# LED_Strip_Board_Schematic.net
KiCad netlist of a schematic drawn in Altium Designer
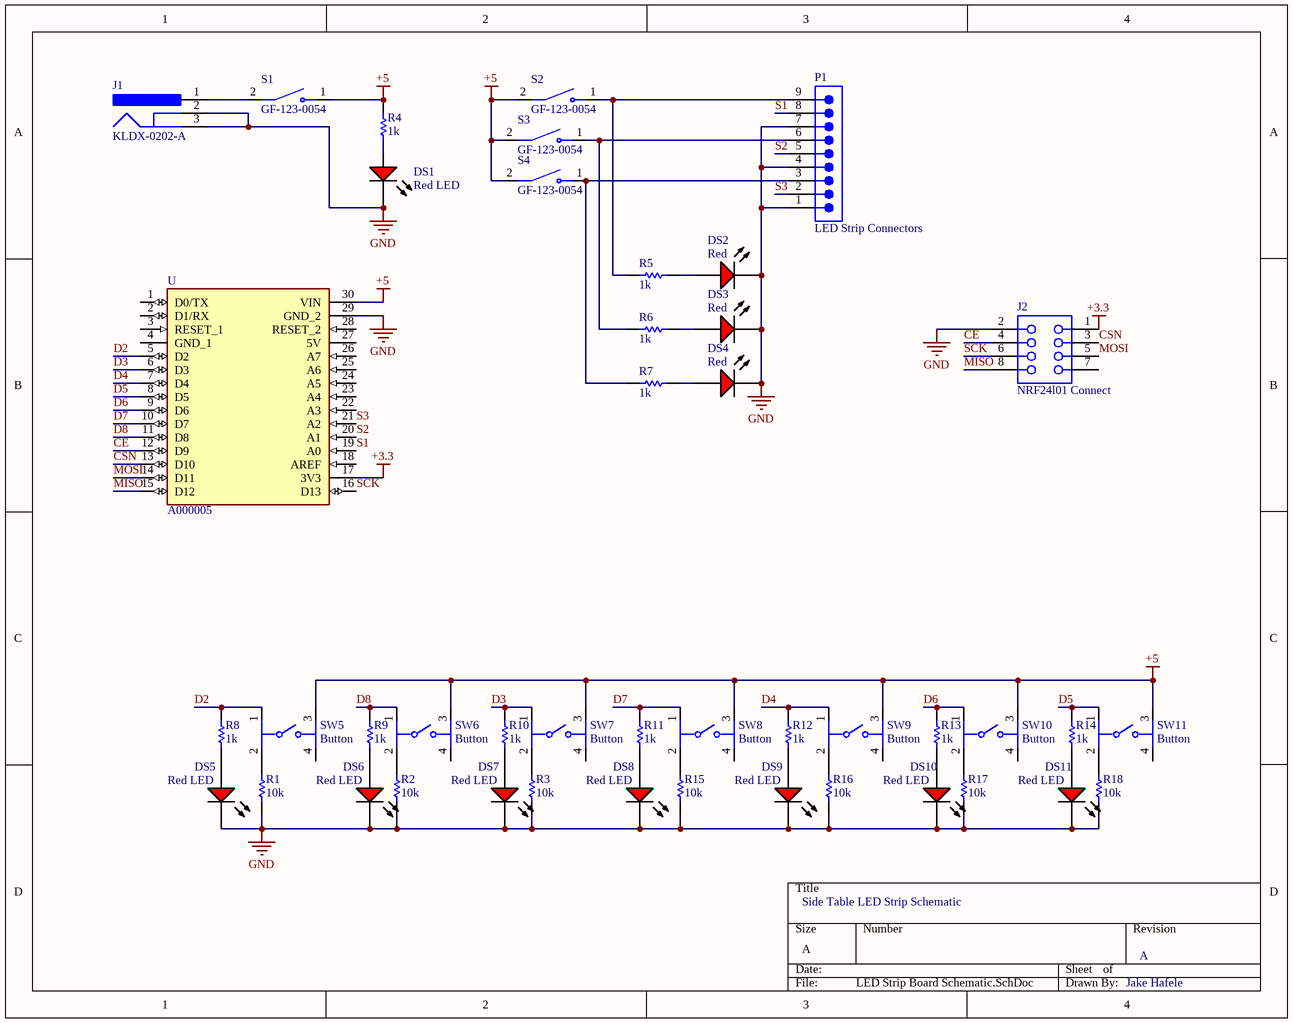
[diagram p0: LED Strip Board Schematic.SchDoc]

(export (version "E")
  (design (tool "Eeschema 10.0.6"))
  (components
    (comp (ref "DS1")
      (value "Red LED")
      (footprint "VISH-TLMS1000_V")
      (description "Low Current LED, 40 mW, 1.8 V, -40 to 100 degC, 2-Pin SMD (0603), RoHS, Tape and Reel")
      (fields (field (name "MANUFACTURER") "Vishay"))
      (libsource (lib "Altium Content Vault") (part "LED-RED-AK-2"))
    )
    (comp (ref "DS2")
      (value "Red")
      (footprint "VISH-TLMS1000_V")
      (description "Low Current LED, 40 mW, 1.8 V, -40 to 100 degC, 2-Pin SMD (0603), RoHS, Tape and Reel")
      (fields (field (name "MANUFACTURER") "Vishay"))
      (libsource (lib "Altium Content Vault") (part "LED-RED-AK-2"))
    )
    (comp (ref "DS3")
      (value "Red")
      (footprint "VISH-TLMS1000_V")
      (description "Low Current LED, 40 mW, 1.8 V, -40 to 100 degC, 2-Pin SMD (0603), RoHS, Tape and Reel")
      (fields (field (name "MANUFACTURER") "Vishay"))
      (libsource (lib "Altium Content Vault") (part "LED-RED-AK-2"))
    )
    (comp (ref "DS4")
      (value "Red")
      (footprint "VISH-TLMS1000_V")
      (description "Low Current LED, 40 mW, 1.8 V, -40 to 100 degC, 2-Pin SMD (0603), RoHS, Tape and Reel")
      (fields (field (name "MANUFACTURER") "Vishay"))
      (libsource (lib "Altium Content Vault") (part "LED-RED-AK-2"))
    )
    (comp (ref "DS5")
      (value "Red LED")
      (footprint "VISH-TLMS1000_V")
      (description "Low Current LED, 40 mW, 1.8 V, -40 to 100 degC, 2-Pin SMD (0603), RoHS, Tape and Reel")
      (fields (field (name "MANUFACTURER") "Vishay"))
      (libsource (lib "Altium Content Vault") (part "LED-RED-AK-2"))
    )
    (comp (ref "DS6")
      (value "Red LED")
      (footprint "VISH-TLMS1000_V")
      (description "Low Current LED, 40 mW, 1.8 V, -40 to 100 degC, 2-Pin SMD (0603), RoHS, Tape and Reel")
      (fields (field (name "MANUFACTURER") "Vishay"))
      (libsource (lib "Altium Content Vault") (part "LED-RED-AK-2"))
    )
    (comp (ref "DS7")
      (value "Red LED")
      (footprint "VISH-TLMS1000_V")
      (description "Low Current LED, 40 mW, 1.8 V, -40 to 100 degC, 2-Pin SMD (0603), RoHS, Tape and Reel")
      (fields (field (name "MANUFACTURER") "Vishay"))
      (libsource (lib "Altium Content Vault") (part "LED-RED-AK-2"))
    )
    (comp (ref "DS8")
      (value "Red LED")
      (footprint "VISH-TLMS1000_V")
      (description "Low Current LED, 40 mW, 1.8 V, -40 to 100 degC, 2-Pin SMD (0603), RoHS, Tape and Reel")
      (fields (field (name "MANUFACTURER") "Vishay"))
      (libsource (lib "Altium Content Vault") (part "LED-RED-AK-2"))
    )
    (comp (ref "DS9")
      (value "Red LED")
      (footprint "VISH-TLMS1000_V")
      (description "Low Current LED, 40 mW, 1.8 V, -40 to 100 degC, 2-Pin SMD (0603), RoHS, Tape and Reel")
      (fields (field (name "MANUFACTURER") "Vishay"))
      (libsource (lib "Altium Content Vault") (part "LED-RED-AK-2"))
    )
    (comp (ref "DS10")
      (value "Red LED")
      (footprint "VISH-TLMS1000_V")
      (description "Low Current LED, 40 mW, 1.8 V, -40 to 100 degC, 2-Pin SMD (0603), RoHS, Tape and Reel")
      (fields (field (name "MANUFACTURER") "Vishay"))
      (libsource (lib "Altium Content Vault") (part "LED-RED-AK-2"))
    )
    (comp (ref "DS11")
      (value "Red LED")
      (footprint "VISH-TLMS1000_V")
      (description "Low Current LED, 40 mW, 1.8 V, -40 to 100 degC, 2-Pin SMD (0603), RoHS, Tape and Reel")
      (fields (field (name "MANUFACTURER") "Vishay"))
      (libsource (lib "Altium Content Vault") (part "LED-RED-AK-2"))
    )
    (comp (ref "J1")
      (value "KLDX-0202-A")
      (footprint "KYCN-KLDX-0202-A_V")
      (description "DC Power Jack, 24 V, 3.5 A, -25 to 85 degC, 3-Pin THD, RoHS")
      (fields (field (name "MANUFACTURER") "Kycon"))
      (libsource (lib "Altium Content Vault") (part "JACK-2CD3-RN"))
    )
    (comp (ref "J2")
      (value "NRF24l01 Connect")
      (footprint "SMTC-SSW-104-01-X-D")
      (description "SQ Post Socket, Through-hole, Vertical, -55 to 105 degC, 2.54mm Pitch, 8-Pin, Female, RoHS")
      (fields (field (name "PARTNUMBER") "SSW-104-01-T-D") (field (name "MANUFACTURER") "Samtec"))
      (libsource (lib "Altium Content Vault") (part "SMTC-SSW-104-X-X-D"))
    )
    (comp (ref "P1")
      (value "LED Strip Connectors")
      (footprint "SMTC-TSM-109-01-X-SV")
      (description "0.025\" SQ Post Header, Surface Mount, Vertical, -55 to 125 degC, 2.54 mm Pitch, 9-Pin, Male, RoHS")
      (fields (field (name "MANUFACTURER") "Samtec") (field (name "PARTNUMBER") "TSM-109-01-L-SV"))
      (libsource (lib "Altium Content Vault") (part "SMTC-TSM-109-01-X-SV"))
    )
    (comp (ref "R1")
      (value "10k")
      (footprint "RESC2013X70X40ML20T20")
      (fields (field (name "MANUFACTURER") "Panasonic") (field (name "PART NUMBER") "ERJ-6ENF1002V"))
      (libsource (lib "Altium Content Vault") (part "RES"))
    )
    (comp (ref "R2")
      (value "10k")
      (footprint "RESC2013X70X40ML20T20")
      (fields (field (name "MANUFACTURER") "Panasonic") (field (name "PART NUMBER") "ERJ-6ENF1002V"))
      (libsource (lib "Altium Content Vault") (part "RES"))
    )
    (comp (ref "R3")
      (value "10k")
      (footprint "RESC2013X70X40ML20T20")
      (fields (field (name "MANUFACTURER") "Panasonic") (field (name "PART NUMBER") "ERJ-6ENF1002V"))
      (libsource (lib "Altium Content Vault") (part "RES"))
    )
    (comp (ref "R4")
      (value "1k")
      (footprint "RESC2013X60X30ML20T20")
      (fields (field (name "PART NUMBER") "RK73B2ATTD102J") (field (name "MANUFACTURER") "KOA Speer"))
      (libsource (lib "Altium Content Vault") (part "RES"))
    )
    (comp (ref "R5")
      (value "1k")
      (footprint "RESC2013X60X30ML20T20")
      (fields (field (name "PART NUMBER") "RK73B2ATTD102J") (field (name "MANUFACTURER") "KOA Speer"))
      (libsource (lib "Altium Content Vault") (part "RES"))
    )
    (comp (ref "R6")
      (value "1k")
      (footprint "RESC2013X60X30ML20T20")
      (fields (field (name "PART NUMBER") "RK73B2ATTD102J") (field (name "MANUFACTURER") "KOA Speer"))
      (libsource (lib "Altium Content Vault") (part "RES"))
    )
    (comp (ref "R7")
      (value "1k")
      (footprint "RESC2013X60X30ML20T20")
      (fields (field (name "PART NUMBER") "RK73B2ATTD102J") (field (name "MANUFACTURER") "KOA Speer"))
      (libsource (lib "Altium Content Vault") (part "RES"))
    )
    (comp (ref "R8")
      (value "1k")
      (footprint "RESC2013X60X30ML20T20")
      (fields (field (name "PART NUMBER") "RK73B2ATTD102J") (field (name "MANUFACTURER") "KOA Speer"))
      (libsource (lib "Altium Content Vault") (part "RES"))
    )
    (comp (ref "R9")
      (value "1k")
      (footprint "RESC2013X60X30ML20T20")
      (fields (field (name "PART NUMBER") "RK73B2ATTD102J") (field (name "MANUFACTURER") "KOA Speer"))
      (libsource (lib "Altium Content Vault") (part "RES"))
    )
    (comp (ref "R10")
      (value "1k")
      (footprint "RESC2013X60X30ML20T20")
      (fields (field (name "PART NUMBER") "RK73B2ATTD102J") (field (name "MANUFACTURER") "KOA Speer"))
      (libsource (lib "Altium Content Vault") (part "RES"))
    )
    (comp (ref "R11")
      (value "1k")
      (footprint "RESC2013X60X30ML20T20")
      (fields (field (name "PART NUMBER") "RK73B2ATTD102J") (field (name "MANUFACTURER") "KOA Speer"))
      (libsource (lib "Altium Content Vault") (part "RES"))
    )
    (comp (ref "R12")
      (value "1k")
      (footprint "RESC2013X60X30ML20T20")
      (fields (field (name "PART NUMBER") "RK73B2ATTD102J") (field (name "MANUFACTURER") "KOA Speer"))
      (libsource (lib "Altium Content Vault") (part "RES"))
    )
    (comp (ref "R13")
      (value "1k")
      (footprint "RESC2013X60X30ML20T20")
      (fields (field (name "PART NUMBER") "RK73B2ATTD102J") (field (name "MANUFACTURER") "KOA Speer"))
      (libsource (lib "Altium Content Vault") (part "RES"))
    )
    (comp (ref "R14")
      (value "1k")
      (footprint "RESC2013X60X30ML20T20")
      (fields (field (name "PART NUMBER") "RK73B2ATTD102J") (field (name "MANUFACTURER") "KOA Speer"))
      (libsource (lib "Altium Content Vault") (part "RES"))
    )
    (comp (ref "R15")
      (value "10k")
      (footprint "RESC2013X70X40ML20T20")
      (fields (field (name "MANUFACTURER") "Panasonic") (field (name "PART NUMBER") "ERJ-6ENF1002V"))
      (libsource (lib "Altium Content Vault") (part "RES"))
    )
    (comp (ref "R16")
      (value "10k")
      (footprint "RESC2013X70X40ML20T20")
      (fields (field (name "MANUFACTURER") "Panasonic") (field (name "PART NUMBER") "ERJ-6ENF1002V"))
      (libsource (lib "Altium Content Vault") (part "RES"))
    )
    (comp (ref "R17")
      (value "10k")
      (footprint "RESC2013X70X40ML20T20")
      (fields (field (name "MANUFACTURER") "Panasonic") (field (name "PART NUMBER") "ERJ-6ENF1002V"))
      (libsource (lib "Altium Content Vault") (part "RES"))
    )
    (comp (ref "R18")
      (value "10k")
      (footprint "RESC2013X70X40ML20T20")
      (fields (field (name "MANUFACTURER") "Panasonic") (field (name "PART NUMBER") "ERJ-6ENF1002V"))
      (libsource (lib "Altium Content Vault") (part "RES"))
    )
    (comp (ref "S1")
      (value "GF-123-0054")
      (footprint "SW_GF-123-0054")
      (description "Slide Switch SPST Through Hole")
      (fields (field (name "MF") "CW Industries"))
      (libsource (lib "GF-123-0054") (part "GF-123-0054"))
    )
    (comp (ref "S2")
      (value "GF-123-0054")
      (footprint "SW_GF-123-0054")
      (description "Slide Switch SPST Through Hole")
      (fields (field (name "MF") "CW Industries"))
      (libsource (lib "GF-123-0054") (part "GF-123-0054"))
    )
    (comp (ref "S3")
      (value "GF-123-0054")
      (footprint "SW_GF-123-0054")
      (description "Slide Switch SPST Through Hole")
      (fields (field (name "MF") "CW Industries"))
      (libsource (lib "GF-123-0054") (part "GF-123-0054"))
    )
    (comp (ref "S4")
      (value "GF-123-0054")
      (footprint "SW_GF-123-0054")
      (description "Slide Switch SPST Through Hole")
      (fields (field (name "MF") "CW Industries"))
      (libsource (lib "GF-123-0054") (part "GF-123-0054"))
    )
    (comp (ref "SW5")
      (value "Button")
      (footprint "FP-1825910-2-0")
      (description "SWITCH TACTILE SPST-NO 0.05A 24V")
      (fields
        (field (name "OCTOPART") "https://octopart.com/1825910-2-te+connectivity-42270502")
        (field (name "MANUFACTURER") "TE")
      )
      (libsource (lib "Altium Content Vault") (part "b8895f3f4cefb76e1819d2863dba89b"))
    )
    (comp (ref "SW6")
      (value "Button")
      (footprint "FP-1825910-2-0")
      (description "SWITCH TACTILE SPST-NO 0.05A 24V")
      (fields
        (field (name "OCTOPART") "https://octopart.com/1825910-2-te+connectivity-42270502")
        (field (name "MANUFACTURER") "TE")
      )
      (libsource (lib "Altium Content Vault") (part "b8895f3f4cefb76e1819d2863dba89b"))
    )
    (comp (ref "SW7")
      (value "Button")
      (footprint "FP-1825910-2-0")
      (description "SWITCH TACTILE SPST-NO 0.05A 24V")
      (fields
        (field (name "OCTOPART") "https://octopart.com/1825910-2-te+connectivity-42270502")
        (field (name "MANUFACTURER") "TE")
      )
      (libsource (lib "Altium Content Vault") (part "b8895f3f4cefb76e1819d2863dba89b"))
    )
    (comp (ref "SW8")
      (value "Button")
      (footprint "FP-1825910-2-0")
      (description "SWITCH TACTILE SPST-NO 0.05A 24V")
      (fields
        (field (name "OCTOPART") "https://octopart.com/1825910-2-te+connectivity-42270502")
        (field (name "MANUFACTURER") "TE")
      )
      (libsource (lib "Altium Content Vault") (part "b8895f3f4cefb76e1819d2863dba89b"))
    )
    (comp (ref "SW9")
      (value "Button")
      (footprint "FP-1825910-2-0")
      (description "SWITCH TACTILE SPST-NO 0.05A 24V")
      (fields
        (field (name "OCTOPART") "https://octopart.com/1825910-2-te+connectivity-42270502")
        (field (name "MANUFACTURER") "TE")
      )
      (libsource (lib "Altium Content Vault") (part "b8895f3f4cefb76e1819d2863dba89b"))
    )
    (comp (ref "SW10")
      (value "Button")
      (footprint "FP-1825910-2-0")
      (description "SWITCH TACTILE SPST-NO 0.05A 24V")
      (fields
        (field (name "OCTOPART") "https://octopart.com/1825910-2-te+connectivity-42270502")
        (field (name "MANUFACTURER") "TE")
      )
      (libsource (lib "Altium Content Vault") (part "b8895f3f4cefb76e1819d2863dba89b"))
    )
    (comp (ref "SW11")
      (value "Button")
      (footprint "FP-1825910-2-0")
      (description "SWITCH TACTILE SPST-NO 0.05A 24V")
      (fields
        (field (name "OCTOPART") "https://octopart.com/1825910-2-te+connectivity-42270502")
        (field (name "MANUFACTURER") "TE")
      )
      (libsource (lib "Altium Content Vault") (part "b8895f3f4cefb76e1819d2863dba89b"))
    )
    (comp (ref "U")
      (value "A000005")
      (footprint "MODULE_A000005")
      (description "CLOCK SAW OSCILLATOR SEAM7050 T&")
      (fields (field (name "DIGI-KEY_PART_NUMBER") "SPA000005J-ND") (field (name "MF") "Arduino"))
      (libsource (lib "A000005") (part "A000005"))
    )
  )
  (nets
    (net (code "1") (name "+3.3") (class "Default")
      (node (ref "J2") (pin "1") (pinfunction "1_1") (pintype "passive"))
      (node (ref "U") (pin "17") (pinfunction "3V3_17") (pintype "power_in"))
    )
    (net (code "2") (name "+5") (class "Default")
      (node (ref "R4") (pin "2") (pinfunction "2_2") (pintype "passive"))
      (node (ref "S1") (pin "1") (pinfunction "1_1") (pintype "passive"))
      (node (ref "S2") (pin "2") (pinfunction "2_2") (pintype "passive"))
      (node (ref "S3") (pin "2") (pinfunction "2_2") (pintype "passive"))
      (node (ref "S4") (pin "2") (pinfunction "2_2") (pintype "passive"))
      (node (ref "SW10") (pin "3") (pinfunction "3_3") (pintype "passive"))
      (node (ref "SW11") (pin "3") (pinfunction "3_3") (pintype "passive"))
      (node (ref "SW5") (pin "3") (pinfunction "3_3") (pintype "passive"))
      (node (ref "SW6") (pin "3") (pinfunction "3_3") (pintype "passive"))
      (node (ref "SW7") (pin "3") (pinfunction "3_3") (pintype "passive"))
      (node (ref "SW8") (pin "3") (pinfunction "3_3") (pintype "passive"))
      (node (ref "SW9") (pin "3") (pinfunction "3_3") (pintype "passive"))
      (node (ref "U") (pin "30") (pinfunction "VIN_30") (pintype "power_in"))
    )
    (net (code "3") (name "/CE") (class "Default")
      (node (ref "J2") (pin "4") (pinfunction "4_4") (pintype "passive"))
      (node (ref "U") (pin "12") (pinfunction "D9_12") (pintype "bidirectional"))
    )
    (net (code "4") (name "/CSN") (class "Default")
      (node (ref "J2") (pin "3") (pinfunction "3_3") (pintype "passive"))
      (node (ref "U") (pin "13") (pinfunction "D10_13") (pintype "bidirectional"))
    )
    (net (code "5") (name "/D2") (class "Default")
      (node (ref "R8") (pin "2") (pinfunction "2_2") (pintype "passive"))
      (node (ref "SW5") (pin "1") (pinfunction "1_1") (pintype "passive"))
      (node (ref "U") (pin "5") (pinfunction "D2_5") (pintype "bidirectional"))
    )
    (net (code "6") (name "/D3") (class "Default")
      (node (ref "R10") (pin "2") (pinfunction "2_2") (pintype "passive"))
      (node (ref "SW7") (pin "1") (pinfunction "1_1") (pintype "passive"))
      (node (ref "U") (pin "6") (pinfunction "D3_6") (pintype "bidirectional"))
    )
    (net (code "7") (name "/D4") (class "Default")
      (node (ref "R12") (pin "2") (pinfunction "2_2") (pintype "passive"))
      (node (ref "SW9") (pin "1") (pinfunction "1_1") (pintype "passive"))
      (node (ref "U") (pin "7") (pinfunction "D4_7") (pintype "bidirectional"))
    )
    (net (code "8") (name "/D5") (class "Default")
      (node (ref "R14") (pin "2") (pinfunction "2_2") (pintype "passive"))
      (node (ref "SW11") (pin "1") (pinfunction "1_1") (pintype "passive"))
      (node (ref "U") (pin "8") (pinfunction "D5_8") (pintype "bidirectional"))
    )
    (net (code "9") (name "/D6") (class "Default")
      (node (ref "R13") (pin "2") (pinfunction "2_2") (pintype "passive"))
      (node (ref "SW10") (pin "1") (pinfunction "1_1") (pintype "passive"))
      (node (ref "U") (pin "9") (pinfunction "D6_9") (pintype "bidirectional"))
    )
    (net (code "10") (name "/D7") (class "Default")
      (node (ref "R11") (pin "2") (pinfunction "2_2") (pintype "passive"))
      (node (ref "SW8") (pin "1") (pinfunction "1_1") (pintype "passive"))
      (node (ref "U") (pin "10") (pinfunction "D7_10") (pintype "bidirectional"))
    )
    (net (code "11") (name "/D8") (class "Default")
      (node (ref "R9") (pin "2") (pinfunction "2_2") (pintype "passive"))
      (node (ref "SW6") (pin "1") (pinfunction "1_1") (pintype "passive"))
      (node (ref "U") (pin "11") (pinfunction "D8_11") (pintype "bidirectional"))
    )
    (net (code "12") (name "/MISO") (class "Default")
      (node (ref "J2") (pin "8") (pinfunction "8_8") (pintype "passive"))
      (node (ref "U") (pin "15") (pinfunction "D12_15") (pintype "bidirectional"))
    )
    (net (code "13") (name "/MOSI") (class "Default")
      (node (ref "J2") (pin "5") (pinfunction "5_5") (pintype "passive"))
      (node (ref "U") (pin "14") (pinfunction "D11_14") (pintype "bidirectional"))
    )
    (net (code "14") (name "/S1") (class "Default")
      (node (ref "P1") (pin "8") (pinfunction "8_8") (pintype "passive"))
      (node (ref "U") (pin "19") (pinfunction "A0_19") (pintype "input"))
    )
    (net (code "15") (name "/S2") (class "Default")
      (node (ref "P1") (pin "5") (pinfunction "5_5") (pintype "passive"))
      (node (ref "U") (pin "20") (pinfunction "A1_20") (pintype "input"))
    )
    (net (code "16") (name "/S3") (class "Default")
      (node (ref "P1") (pin "2") (pinfunction "2_2") (pintype "passive"))
      (node (ref "U") (pin "21") (pinfunction "A2_21") (pintype "input"))
    )
    (net (code "17") (name "/SCK") (class "Default")
      (node (ref "J2") (pin "6") (pinfunction "6_6") (pintype "passive"))
      (node (ref "U") (pin "16") (pinfunction "D13_16") (pintype "bidirectional"))
    )
    (net (code "18") (name "GND") (class "Default")
      (node (ref "DS1") (pin "2") (pinfunction "K_2") (pintype "passive"))
      (node (ref "DS10") (pin "2") (pinfunction "K_2") (pintype "passive"))
      (node (ref "DS11") (pin "2") (pinfunction "K_2") (pintype "passive"))
      (node (ref "DS2") (pin "2") (pinfunction "K_2") (pintype "passive"))
      (node (ref "DS3") (pin "2") (pinfunction "K_2") (pintype "passive"))
      (node (ref "DS4") (pin "2") (pinfunction "K_2") (pintype "passive"))
      (node (ref "DS5") (pin "2") (pinfunction "K_2") (pintype "passive"))
      (node (ref "DS6") (pin "2") (pinfunction "K_2") (pintype "passive"))
      (node (ref "DS7") (pin "2") (pinfunction "K_2") (pintype "passive"))
      (node (ref "DS8") (pin "2") (pinfunction "K_2") (pintype "passive"))
      (node (ref "DS9") (pin "2") (pinfunction "K_2") (pintype "passive"))
      (node (ref "J1") (pin "2") (pinfunction "2_2") (pintype "passive"))
      (node (ref "J1") (pin "3") (pinfunction "3_3") (pintype "passive"))
      (node (ref "J2") (pin "2") (pinfunction "2_2") (pintype "passive"))
      (node (ref "P1") (pin "1") (pinfunction "1_1") (pintype "passive"))
      (node (ref "P1") (pin "4") (pinfunction "4_4") (pintype "passive"))
      (node (ref "P1") (pin "7") (pinfunction "7_7") (pintype "passive"))
      (node (ref "R1") (pin "2") (pinfunction "2_2") (pintype "passive"))
      (node (ref "R15") (pin "2") (pinfunction "2_2") (pintype "passive"))
      (node (ref "R16") (pin "2") (pinfunction "2_2") (pintype "passive"))
      (node (ref "R17") (pin "2") (pinfunction "2_2") (pintype "passive"))
      (node (ref "R18") (pin "2") (pinfunction "2_2") (pintype "passive"))
      (node (ref "R2") (pin "2") (pinfunction "2_2") (pintype "passive"))
      (node (ref "R3") (pin "2") (pinfunction "2_2") (pintype "passive"))
      (node (ref "U") (pin "29") (pinfunction "GND_2_29") (pintype "power_in"))
    )
    (net (code "19") (name "Net-(DS1-A)") (class "Default")
      (node (ref "DS1") (pin "1") (pinfunction "A_1") (pintype "passive"))
      (node (ref "R4") (pin "1") (pinfunction "1_1") (pintype "passive"))
    )
    (net (code "20") (name "Net-(DS2-A)") (class "Default")
      (node (ref "DS2") (pin "1") (pinfunction "A_1") (pintype "passive"))
      (node (ref "R5") (pin "1") (pinfunction "1_1") (pintype "passive"))
    )
    (net (code "21") (name "Net-(DS3-A)") (class "Default")
      (node (ref "DS3") (pin "1") (pinfunction "A_1") (pintype "passive"))
      (node (ref "R6") (pin "1") (pinfunction "1_1") (pintype "passive"))
    )
    (net (code "22") (name "Net-(DS4-A)") (class "Default")
      (node (ref "DS4") (pin "1") (pinfunction "A_1") (pintype "passive"))
      (node (ref "R7") (pin "1") (pinfunction "1_1") (pintype "passive"))
    )
    (net (code "23") (name "Net-(DS5-A)") (class "Default")
      (node (ref "DS5") (pin "1") (pinfunction "A_1") (pintype "passive"))
      (node (ref "R8") (pin "1") (pinfunction "1_1") (pintype "passive"))
    )
    (net (code "24") (name "Net-(DS6-A)") (class "Default")
      (node (ref "DS6") (pin "1") (pinfunction "A_1") (pintype "passive"))
      (node (ref "R9") (pin "1") (pinfunction "1_1") (pintype "passive"))
    )
    (net (code "25") (name "Net-(DS7-A)") (class "Default")
      (node (ref "DS7") (pin "1") (pinfunction "A_1") (pintype "passive"))
      (node (ref "R10") (pin "1") (pinfunction "1_1") (pintype "passive"))
    )
    (net (code "26") (name "Net-(DS8-A)") (class "Default")
      (node (ref "DS8") (pin "1") (pinfunction "A_1") (pintype "passive"))
      (node (ref "R11") (pin "1") (pinfunction "1_1") (pintype "passive"))
    )
    (net (code "27") (name "Net-(DS9-A)") (class "Default")
      (node (ref "DS9") (pin "1") (pinfunction "A_1") (pintype "passive"))
      (node (ref "R12") (pin "1") (pinfunction "1_1") (pintype "passive"))
    )
    (net (code "28") (name "Net-(DS10-A)") (class "Default")
      (node (ref "DS10") (pin "1") (pinfunction "A_1") (pintype "passive"))
      (node (ref "R13") (pin "1") (pinfunction "1_1") (pintype "passive"))
    )
    (net (code "29") (name "Net-(DS11-A)") (class "Default")
      (node (ref "DS11") (pin "1") (pinfunction "A_1") (pintype "passive"))
      (node (ref "R14") (pin "1") (pinfunction "1_1") (pintype "passive"))
    )
    (net (code "30") (name "Net-(J1-Pad1)") (class "Default")
      (node (ref "J1") (pin "1") (pinfunction "1_1") (pintype "passive"))
      (node (ref "S1") (pin "2") (pinfunction "2_2") (pintype "passive"))
    )
    (net (code "31") (name "Net-(P1-Pad3)") (class "Default")
      (node (ref "P1") (pin "3") (pinfunction "3_3") (pintype "passive"))
      (node (ref "R7") (pin "2") (pinfunction "2_2") (pintype "passive"))
      (node (ref "S4") (pin "1") (pinfunction "1_1") (pintype "passive"))
    )
    (net (code "32") (name "Net-(P1-Pad6)") (class "Default")
      (node (ref "P1") (pin "6") (pinfunction "6_6") (pintype "passive"))
      (node (ref "R6") (pin "2") (pinfunction "2_2") (pintype "passive"))
      (node (ref "S3") (pin "1") (pinfunction "1_1") (pintype "passive"))
    )
    (net (code "33") (name "Net-(P1-Pad9)") (class "Default")
      (node (ref "P1") (pin "9") (pinfunction "9_9") (pintype "passive"))
      (node (ref "R5") (pin "2") (pinfunction "2_2") (pintype "passive"))
      (node (ref "S2") (pin "1") (pinfunction "1_1") (pintype "passive"))
    )
    (net (code "34") (name "Net-(R1-Pad1)") (class "Default")
      (node (ref "R1") (pin "1") (pinfunction "1_1") (pintype "passive"))
      (node (ref "SW5") (pin "2") (pinfunction "2_2") (pintype "passive"))
    )
    (net (code "35") (name "Net-(R2-Pad1)") (class "Default")
      (node (ref "R2") (pin "1") (pinfunction "1_1") (pintype "passive"))
      (node (ref "SW6") (pin "2") (pinfunction "2_2") (pintype "passive"))
    )
    (net (code "36") (name "Net-(R3-Pad1)") (class "Default")
      (node (ref "R3") (pin "1") (pinfunction "1_1") (pintype "passive"))
      (node (ref "SW7") (pin "2") (pinfunction "2_2") (pintype "passive"))
    )
    (net (code "37") (name "Net-(R15-Pad1)") (class "Default")
      (node (ref "R15") (pin "1") (pinfunction "1_1") (pintype "passive"))
      (node (ref "SW8") (pin "2") (pinfunction "2_2") (pintype "passive"))
    )
    (net (code "38") (name "Net-(R16-Pad1)") (class "Default")
      (node (ref "R16") (pin "1") (pinfunction "1_1") (pintype "passive"))
      (node (ref "SW9") (pin "2") (pinfunction "2_2") (pintype "passive"))
    )
    (net (code "39") (name "Net-(R17-Pad1)") (class "Default")
      (node (ref "R17") (pin "1") (pinfunction "1_1") (pintype "passive"))
      (node (ref "SW10") (pin "2") (pinfunction "2_2") (pintype "passive"))
    )
    (net (code "40") (name "Net-(R18-Pad1)") (class "Default")
      (node (ref "R18") (pin "1") (pinfunction "1_1") (pintype "passive"))
      (node (ref "SW11") (pin "2") (pinfunction "2_2") (pintype "passive"))
    )
    (net (code "41") (name "unconnected-(J2-Pad7)") (class "Default")
      (node (ref "J2") (pin "7") (pinfunction "7_7") (pintype "passive"))
    )
    (net (code "42") (name "unconnected-(SW5-Pad4)") (class "Default")
      (node (ref "SW5") (pin "4") (pinfunction "4_4") (pintype "passive"))
    )
    (net (code "43") (name "unconnected-(SW6-Pad4)") (class "Default")
      (node (ref "SW6") (pin "4") (pinfunction "4_4") (pintype "passive"))
    )
    (net (code "44") (name "unconnected-(SW7-Pad4)") (class "Default")
      (node (ref "SW7") (pin "4") (pinfunction "4_4") (pintype "passive"))
    )
    (net (code "45") (name "unconnected-(SW8-Pad4)") (class "Default")
      (node (ref "SW8") (pin "4") (pinfunction "4_4") (pintype "passive"))
    )
    (net (code "46") (name "unconnected-(SW9-Pad4)") (class "Default")
      (node (ref "SW9") (pin "4") (pinfunction "4_4") (pintype "passive"))
    )
    (net (code "47") (name "unconnected-(SW10-Pad4)") (class "Default")
      (node (ref "SW10") (pin "4") (pinfunction "4_4") (pintype "passive"))
    )
    (net (code "48") (name "unconnected-(SW11-Pad4)") (class "Default")
      (node (ref "SW11") (pin "4") (pinfunction "4_4") (pintype "passive"))
    )
    (net (code "49") (name "unconnected-(U-5V-Pad27)") (class "Default")
      (node (ref "U") (pin "27") (pinfunction "5V_27") (pintype "power_in"))
    )
    (net (code "50") (name "unconnected-(U-A3-Pad22)") (class "Default")
      (node (ref "U") (pin "22") (pinfunction "A3_22") (pintype "input"))
    )
    (net (code "51") (name "unconnected-(U-A4-Pad23)") (class "Default")
      (node (ref "U") (pin "23") (pinfunction "A4_23") (pintype "input"))
    )
    (net (code "52") (name "unconnected-(U-A5-Pad24)") (class "Default")
      (node (ref "U") (pin "24") (pinfunction "A5_24") (pintype "input"))
    )
    (net (code "53") (name "unconnected-(U-A6-Pad25)") (class "Default")
      (node (ref "U") (pin "25") (pinfunction "A6_25") (pintype "input"))
    )
    (net (code "54") (name "unconnected-(U-A7-Pad26)") (class "Default")
      (node (ref "U") (pin "26") (pinfunction "A7_26") (pintype "input"))
    )
    (net (code "55") (name "unconnected-(U-AREF-Pad18)") (class "Default")
      (node (ref "U") (pin "18") (pinfunction "AREF_18") (pintype "input"))
    )
    (net (code "56") (name "unconnected-(U-D0{slash}TX-Pad1)") (class "Default")
      (node (ref "U") (pin "1") (pinfunction "D0/TX_1") (pintype "bidirectional"))
    )
    (net (code "57") (name "unconnected-(U-D1{slash}RX-Pad2)") (class "Default")
      (node (ref "U") (pin "2") (pinfunction "D1/RX_2") (pintype "bidirectional"))
    )
    (net (code "58") (name "unconnected-(U-GND_1-Pad4)") (class "Default")
      (node (ref "U") (pin "4") (pinfunction "GND_1_4") (pintype "power_in"))
    )
    (net (code "59") (name "unconnected-(U-RESET_1-Pad3)") (class "Default")
      (node (ref "U") (pin "3") (pinfunction "RESET_1_3") (pintype "input"))
    )
    (net (code "60") (name "unconnected-(U-RESET_2-Pad28)") (class "Default")
      (node (ref "U") (pin "28") (pinfunction "RESET_2_28") (pintype "input"))
    )
  )
)
